# SAMV71_Xplained_Ultra_MCU_Peripherals.net
KiCad netlist of a schematic drawn in Altium Designer
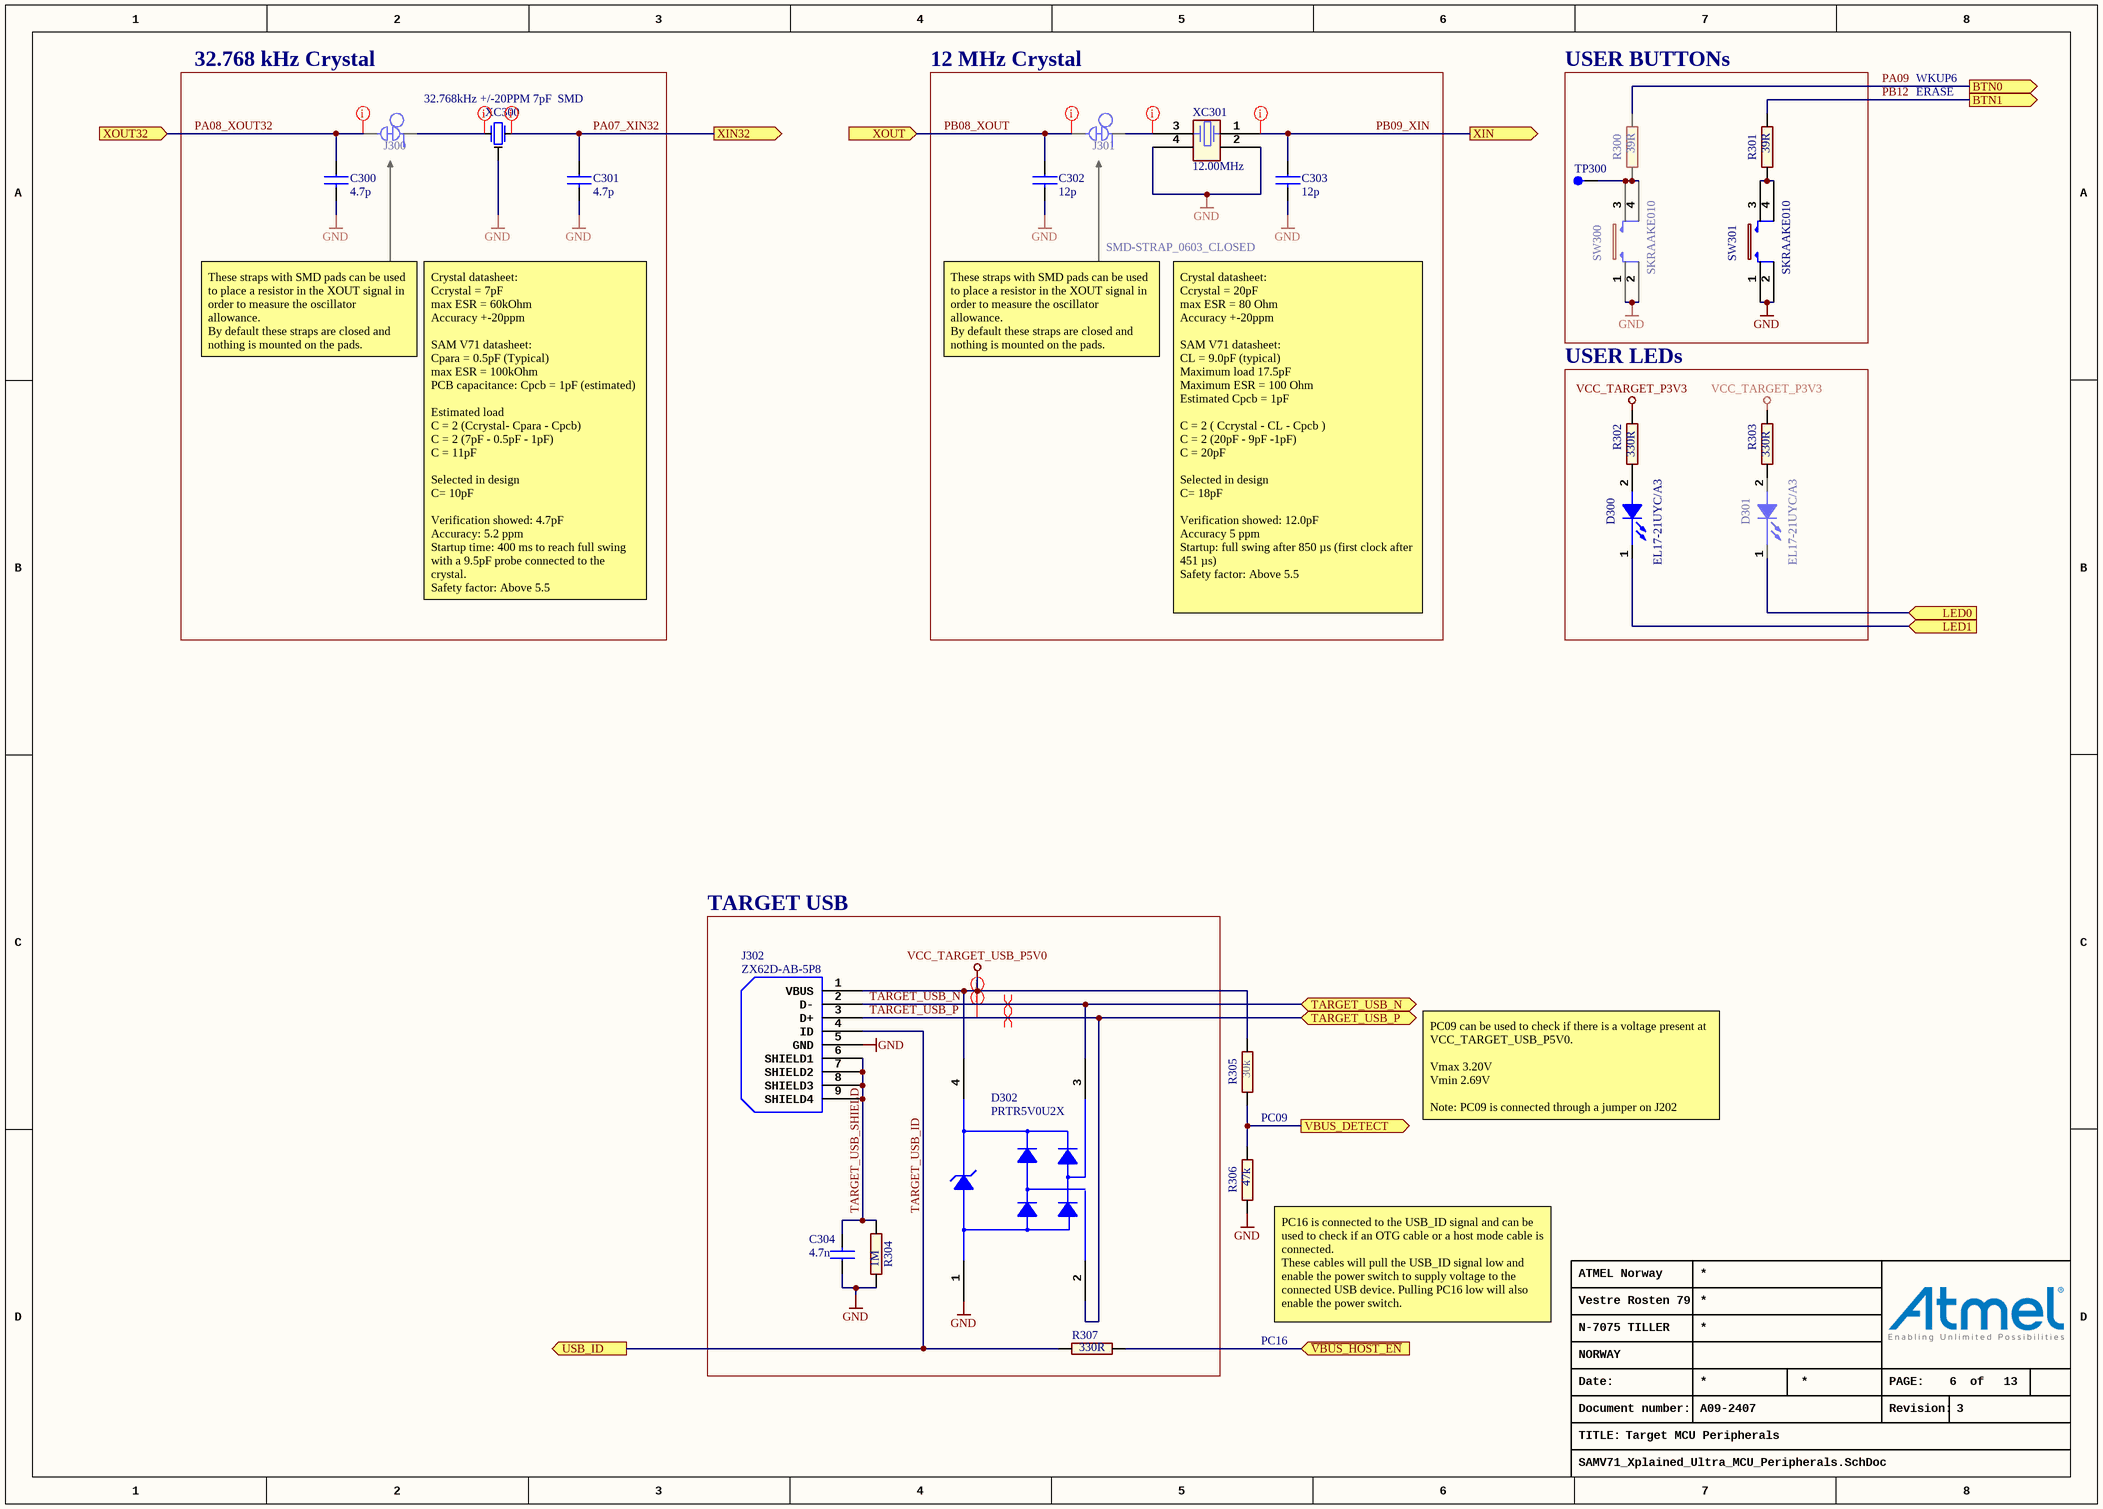
[diagram p0: SAMV71_Xplained_Ultra_MCU_Peripherals.SchDoc]

(export (version "E")
  (design (tool "Eeschema 10.0.6"))
  (components
    (comp (ref "C300")
      (value "4.7p")
      (footprint "AP1-00001")
      (description "Ceramic capacitor, SMD 0402, NP0, 50V, +/-0.25pF")
      (fields (field (name "TOLERANCE") "50V, +/-0.25pF"))
      (libsource (lib "AltiumDbLib") (part "CAP-NONPOL"))
    )
    (comp (ref "C301")
      (value "4.7p")
      (footprint "AP1-00001")
      (description "Ceramic capacitor, SMD 0402, NP0, 50V, +/-0.25pF")
      (fields (field (name "TOLERANCE") "50V, +/-0.25pF"))
      (libsource (lib "AltiumDbLib") (part "CAP-NONPOL"))
    )
    (comp (ref "C302")
      (value "12p")
      (footprint "AP1-00001")
      (description "Ceramic capacitor, SMD 0402, NP0, 50V, +/-5%")
      (fields (field (name "TOLERANCE") "50V, +/-5%"))
      (libsource (lib "AltiumDbLib") (part "CAP-NONPOL"))
    )
    (comp (ref "C303")
      (value "12p")
      (footprint "AP1-00001")
      (description "Ceramic capacitor, SMD 0402, NP0, 50V, +/-5%")
      (fields (field (name "TOLERANCE") "50V, +/-5%"))
      (libsource (lib "AltiumDbLib") (part "CAP-NONPOL"))
    )
    (comp (ref "C304")
      (value "4.7n")
      (footprint "AP1-00053")
      (description "Ceramic capacitor, SMD 0402, X7R, 25V, +/-10%")
      (fields (field (name "TOLERANCE") "25V, +/-10%"))
      (libsource (lib "AltiumDbLib") (part "CAP-NONPOL"))
    )
    (comp (ref "D300")
      (value "EL17-21UYC/A3")
      (footprint "AP4-00013")
      (description "LED, Yellow, Wave length=591nm, SMD 0805, ±70°")
      (fields (field (name "MANUFACTURER") "Everlight") (field (name "MPN") "17-21UYC/S530-A3/TR8"))
      (libsource (lib "AltiumDbLib") (part "LED_12"))
    )
    (comp (ref "D301")
      (value "EL17-21UYC/A3")
      (footprint "AP4-00013")
      (description "LED, Yellow, Wave length=591nm, SMD 0805, ±70°")
      (fields (field (name "MANUFACTURER") "Everlight") (field (name "MPN") "17-21UYC/S530-A3/TR8"))
      (libsource (lib "AltiumDbLib") (part "LED_12"))
    )
    (comp (ref "D302")
      (value "PRTR5V0U2X")
      (footprint "AP4-00001")
      (description "Double rail-to-rail USB ESD protection diode")
      (fields (field (name "MANUFACTURER") "NXP"))
      (libsource (lib "AltiumDbLib") (part "PRTR5V0U2X"))
    )
    (comp (ref "J300")
      (value "~")
      (footprint "AP9-00044")
      (description "Default closed SMD strap, 0603 size")
      (libsource (lib "AltiumDbLib") (part "SMD-STRAP_CLOSED"))
    )
    (comp (ref "J301")
      (value "SMD-STRAP_0603_CLOSED")
      (footprint "AP9-00044")
      (description "Default closed SMD strap, 0603 size")
      (libsource (lib "AltiumDbLib") (part "SMD-STRAP_CLOSED"))
    )
    (comp (ref "J302")
      (value "ZX62D-AB-5P8")
      (footprint "AP8-00852")
      (description "Micro USB AB Connector, Standard SMT + DIP")
      (fields (field (name "MANUFACTURER") "HIROSE") (field (name "Comment") "2,000 pieces per reel"))
      (libsource (lib "AltiumDbLib") (part "USB_AB"))
    )
    (comp (ref "R300")
      (value "39R")
      (footprint "AP2-00011")
      (description "Thick film resistor, SMD 0402, 1/16W, 1%")
      (fields (field (name "TOLERANCE") "1 %"))
      (libsource (lib "") (part "R2_1"))
    )
    (comp (ref "R301")
      (value "39R")
      (footprint "AP2-00011")
      (description "Thick film resistor, SMD 0402, 1/16W, 1%")
      (fields (field (name "TOLERANCE") "1 %"))
      (libsource (lib "") (part "R2_1"))
    )
    (comp (ref "R302")
      (value "330R")
      (footprint "AP2-00000")
      (description "Thick film resistor, SMD 0402, 1/16W, 1%")
      (fields (field (name "TOLERANCE") "1 %"))
      (libsource (lib "AltiumDbLib") (part "R2"))
    )
    (comp (ref "R303")
      (value "330R")
      (footprint "AP2-00000")
      (description "Thick film resistor, SMD 0402, 1/16W, 1%")
      (fields (field (name "TOLERANCE") "1 %"))
      (libsource (lib "AltiumDbLib") (part "R2"))
    )
    (comp (ref "R304")
      (value "1M")
      (footprint "AP2-00011")
      (description "Thick film resistor, SMD 0402, 1/16W, 1%")
      (fields (field (name "TOLERANCE") "1 %"))
      (libsource (lib "") (part "R2_1"))
    )
    (comp (ref "R305")
      (value "30k")
      (footprint "AP2-00000")
      (description "Thick film resistor, SMD 0402, 1/16W, 1%")
      (fields (field (name "TOLERANCE") "1 %"))
      (libsource (lib "AltiumDbLib") (part "R2"))
    )
    (comp (ref "R306")
      (value "47k")
      (footprint "AP2-00000")
      (description "Thick film resistor, SMD 0402, 1/16W, 1%")
      (fields (field (name "TOLERANCE") "1 %"))
      (libsource (lib "AltiumDbLib") (part "R2"))
    )
    (comp (ref "R307")
      (value "330R")
      (footprint "AP2-00000")
      (description "Thick film resistor, SMD 0402, 1/16W, 1%")
      (fields (field (name "TOLERANCE") "1 %"))
      (libsource (lib "") (part "R2_2"))
    )
    (comp (ref "SW300")
      (value "SKRAAKE010")
      (footprint "AP8-00137")
      (description "6.2x6.2 mm SMD tact switch, same as A08-0091 but less force is needed")
      (fields
        (field (name "MANUFACTURER") "ALPS")
        (field (name "Comment") "Can be ordered in low volumes from Mouser")
      )
      (libsource (lib "AltiumDbLib") (part "PUSHBUTTON1"))
    )
    (comp (ref "SW301")
      (value "SKRAAKE010")
      (footprint "AP8-00137")
      (description "6.2x6.2 mm SMD tact switch, same as A08-0091 but less force is needed")
      (fields
        (field (name "MANUFACTURER") "ALPS")
        (field (name "Comment") "Can be ordered in low volumes from Mouser")
      )
      (libsource (lib "AltiumDbLib") (part "PUSHBUTTON1"))
    )
    (comp (ref "TP300")
      (value "~")
      (footprint "AP8-00010")
      (description "Single SMD testpad")
      (libsource (lib "AltiumDbLib") (part "TESTPOINT"))
    )
    (comp (ref "XC300")
      (value "32.768kHz +/-20PPM 7pF  SMD")
      (footprint "AP7-00044")
      (description "32k768 crystal, +-20ppm, CL=7pF, max ESR 60kOhm, SMD")
      (fields (field (name "TOLERANCE") "+/- 20 PPM") (field (name "MANUFACTURER") "Micro Crystal"))
      (libsource (lib "AltiumDbLib") (part "CRYSTAL_2P_metal"))
    )
    (comp (ref "XC301")
      (value "12.00MHz")
      (footprint "AP7-00039")
      (description "Fox FQ5032B 12.0MHz SMD crystal 738B-12")
      (fields (field (name "TOLERANCE") "Â±30ppm") (field (name "MANUFACTURER") "Fox  Electronics"))
      (libsource (lib "AltiumDbLib") (part "CRYSTAL1324"))
    )
  )
  (nets
    (net (code "1") (name "/LED0") (class "Default")
      (node (ref "D301") (pin "1") (pinfunction "CATHODE_1") (pintype "passive"))
    )
    (net (code "2") (name "/LED1") (class "Default")
      (node (ref "D300") (pin "1") (pinfunction "CATHODE_1") (pintype "passive"))
    )
    (net (code "3") (name "/PA07_XIN32") (class "Default")
      (node (ref "C301") (pin "1") (pinfunction "1_1") (pintype "passive"))
      (node (ref "XC300") (pin "2") (pinfunction "2_2") (pintype "passive"))
    )
    (net (code "4") (name "/PA08_XOUT32") (class "Default")
      (node (ref "C300") (pin "1") (pinfunction "1_1") (pintype "passive"))
      (node (ref "J300") (pin "2") (pinfunction "2_2") (pintype "passive"))
    )
    (net (code "5") (name "/PA09") (class "Default")
      (node (ref "R300") (pin "2") (pinfunction "2_2") (pintype "passive"))
    )
    (net (code "6") (name "/PB08_XOUT") (class "Default")
      (node (ref "C302") (pin "1") (pinfunction "1_1") (pintype "passive"))
      (node (ref "J301") (pin "2") (pinfunction "2_2") (pintype "passive"))
    )
    (net (code "7") (name "/PB09_XIN") (class "Default")
      (node (ref "C303") (pin "1") (pinfunction "1_1") (pintype "passive"))
      (node (ref "XC301") (pin "1") (pinfunction "1_1") (pintype "passive"))
    )
    (net (code "8") (name "/PB12") (class "Default")
      (node (ref "R301") (pin "2") (pinfunction "2_2") (pintype "passive"))
    )
    (net (code "9") (name "/TARGET_USB_ID") (class "Default")
      (node (ref "J302") (pin "4") (pinfunction "ID_4") (pintype "passive"))
      (node (ref "R307") (pin "1") (pinfunction "1_1") (pintype "passive"))
    )
    (net (code "10") (name "/TARGET_USB_N") (class "Default")
      (node (ref "D302") (pin "3") (pinfunction "I/O_2_3") (pintype "passive"))
      (node (ref "J302") (pin "2") (pinfunction "D-_2") (pintype "passive"))
    )
    (net (code "11") (name "/TARGET_USB_P") (class "Default")
      (node (ref "D302") (pin "2") (pinfunction "I/O_1_2") (pintype "passive"))
      (node (ref "J302") (pin "3") (pinfunction "D+_3") (pintype "passive"))
    )
    (net (code "12") (name "/TARGET_USB_SHIELD") (class "Default")
      (node (ref "C304") (pin "2") (pinfunction "2_2") (pintype "passive"))
      (node (ref "J302") (pin "6") (pinfunction "SHIELD1_6") (pintype "passive"))
      (node (ref "J302") (pin "7") (pinfunction "SHIELD2_7") (pintype "passive"))
      (node (ref "J302") (pin "8") (pinfunction "SHIELD3_8") (pintype "passive"))
      (node (ref "J302") (pin "9") (pinfunction "SHIELD4_9") (pintype "passive"))
      (node (ref "R304") (pin "2") (pinfunction "2_2") (pintype "passive"))
    )
    (net (code "13") (name "/VBUS_DETECT") (class "Default")
      (node (ref "R305") (pin "1") (pinfunction "1_1") (pintype "passive"))
      (node (ref "R306") (pin "2") (pinfunction "2_2") (pintype "passive"))
    )
    (net (code "14") (name "/~{VBUS_HOST_EN}") (class "Default")
      (node (ref "R307") (pin "2") (pinfunction "2_2") (pintype "passive"))
    )
    (net (code "15") (name "GND") (class "Default")
      (node (ref "C300") (pin "2") (pinfunction "2_2") (pintype "passive"))
      (node (ref "C301") (pin "2") (pinfunction "2_2") (pintype "passive"))
      (node (ref "C302") (pin "2") (pinfunction "2_2") (pintype "passive"))
      (node (ref "C303") (pin "2") (pinfunction "2_2") (pintype "passive"))
      (node (ref "C304") (pin "1") (pinfunction "1_1") (pintype "passive"))
      (node (ref "D302") (pin "1") (pinfunction "GND_1") (pintype "passive"))
      (node (ref "J302") (pin "5") (pinfunction "GND_5") (pintype "passive"))
      (node (ref "R304") (pin "1") (pinfunction "1_1") (pintype "passive"))
      (node (ref "R306") (pin "1") (pinfunction "1_1") (pintype "passive"))
      (node (ref "SW300") (pin "1") (pinfunction "1_1") (pintype "passive"))
      (node (ref "SW300") (pin "2") (pinfunction "2_2") (pintype "passive"))
      (node (ref "SW301") (pin "1") (pinfunction "1_1") (pintype "passive"))
      (node (ref "SW301") (pin "2") (pinfunction "2_2") (pintype "passive"))
      (node (ref "XC300") (pin "3") (pinfunction "3_3") (pintype "passive"))
      (node (ref "XC301") (pin "2") (pinfunction "2_2") (pintype "passive"))
      (node (ref "XC301") (pin "4") (pinfunction "4_4") (pintype "passive"))
    )
    (net (code "16") (name "Net-(D300-ANODE)") (class "Default")
      (node (ref "D300") (pin "2") (pinfunction "ANODE_2") (pintype "passive"))
      (node (ref "R302") (pin "1") (pinfunction "1_1") (pintype "passive"))
    )
    (net (code "17") (name "Net-(D301-ANODE)") (class "Default")
      (node (ref "D301") (pin "2") (pinfunction "ANODE_2") (pintype "passive"))
      (node (ref "R303") (pin "1") (pinfunction "1_1") (pintype "passive"))
    )
    (net (code "18") (name "Net-(J300-Pad1)") (class "Default")
      (node (ref "J300") (pin "1") (pinfunction "1_1") (pintype "passive"))
      (node (ref "XC300") (pin "1") (pinfunction "1_1") (pintype "passive"))
    )
    (net (code "19") (name "Net-(J301-Pad1)") (class "Default")
      (node (ref "J301") (pin "1") (pinfunction "1_1") (pintype "passive"))
      (node (ref "XC301") (pin "3") (pinfunction "3_3") (pintype "passive"))
    )
    (net (code "20") (name "Net-(R300-Pad1)") (class "Default")
      (node (ref "R300") (pin "1") (pinfunction "1_1") (pintype "passive"))
      (node (ref "SW300") (pin "3") (pinfunction "3_3") (pintype "passive"))
      (node (ref "SW300") (pin "4") (pinfunction "4_4") (pintype "passive"))
      (node (ref "TP300") (pin "1") (pinfunction "1_1") (pintype "passive"))
    )
    (net (code "21") (name "Net-(R301-Pad1)") (class "Default")
      (node (ref "R301") (pin "1") (pinfunction "1_1") (pintype "passive"))
      (node (ref "SW301") (pin "3") (pinfunction "3_3") (pintype "passive"))
      (node (ref "SW301") (pin "4") (pinfunction "4_4") (pintype "passive"))
    )
    (net (code "22") (name "VCC_TARGET_P3V3") (class "Default")
      (node (ref "R302") (pin "2") (pinfunction "2_2") (pintype "passive"))
      (node (ref "R303") (pin "2") (pinfunction "2_2") (pintype "passive"))
    )
    (net (code "23") (name "VCC_TARGET_USB_P5V0") (class "Default")
      (node (ref "D302") (pin "4") (pinfunction "VCC_4") (pintype "passive"))
      (node (ref "J302") (pin "1") (pinfunction "VBUS_1") (pintype "passive"))
      (node (ref "R305") (pin "2") (pinfunction "2_2") (pintype "passive"))
    )
  )
)
